# DCDC_Buck_Boost.net
KiCad netlist of a schematic drawn in Altium Designer
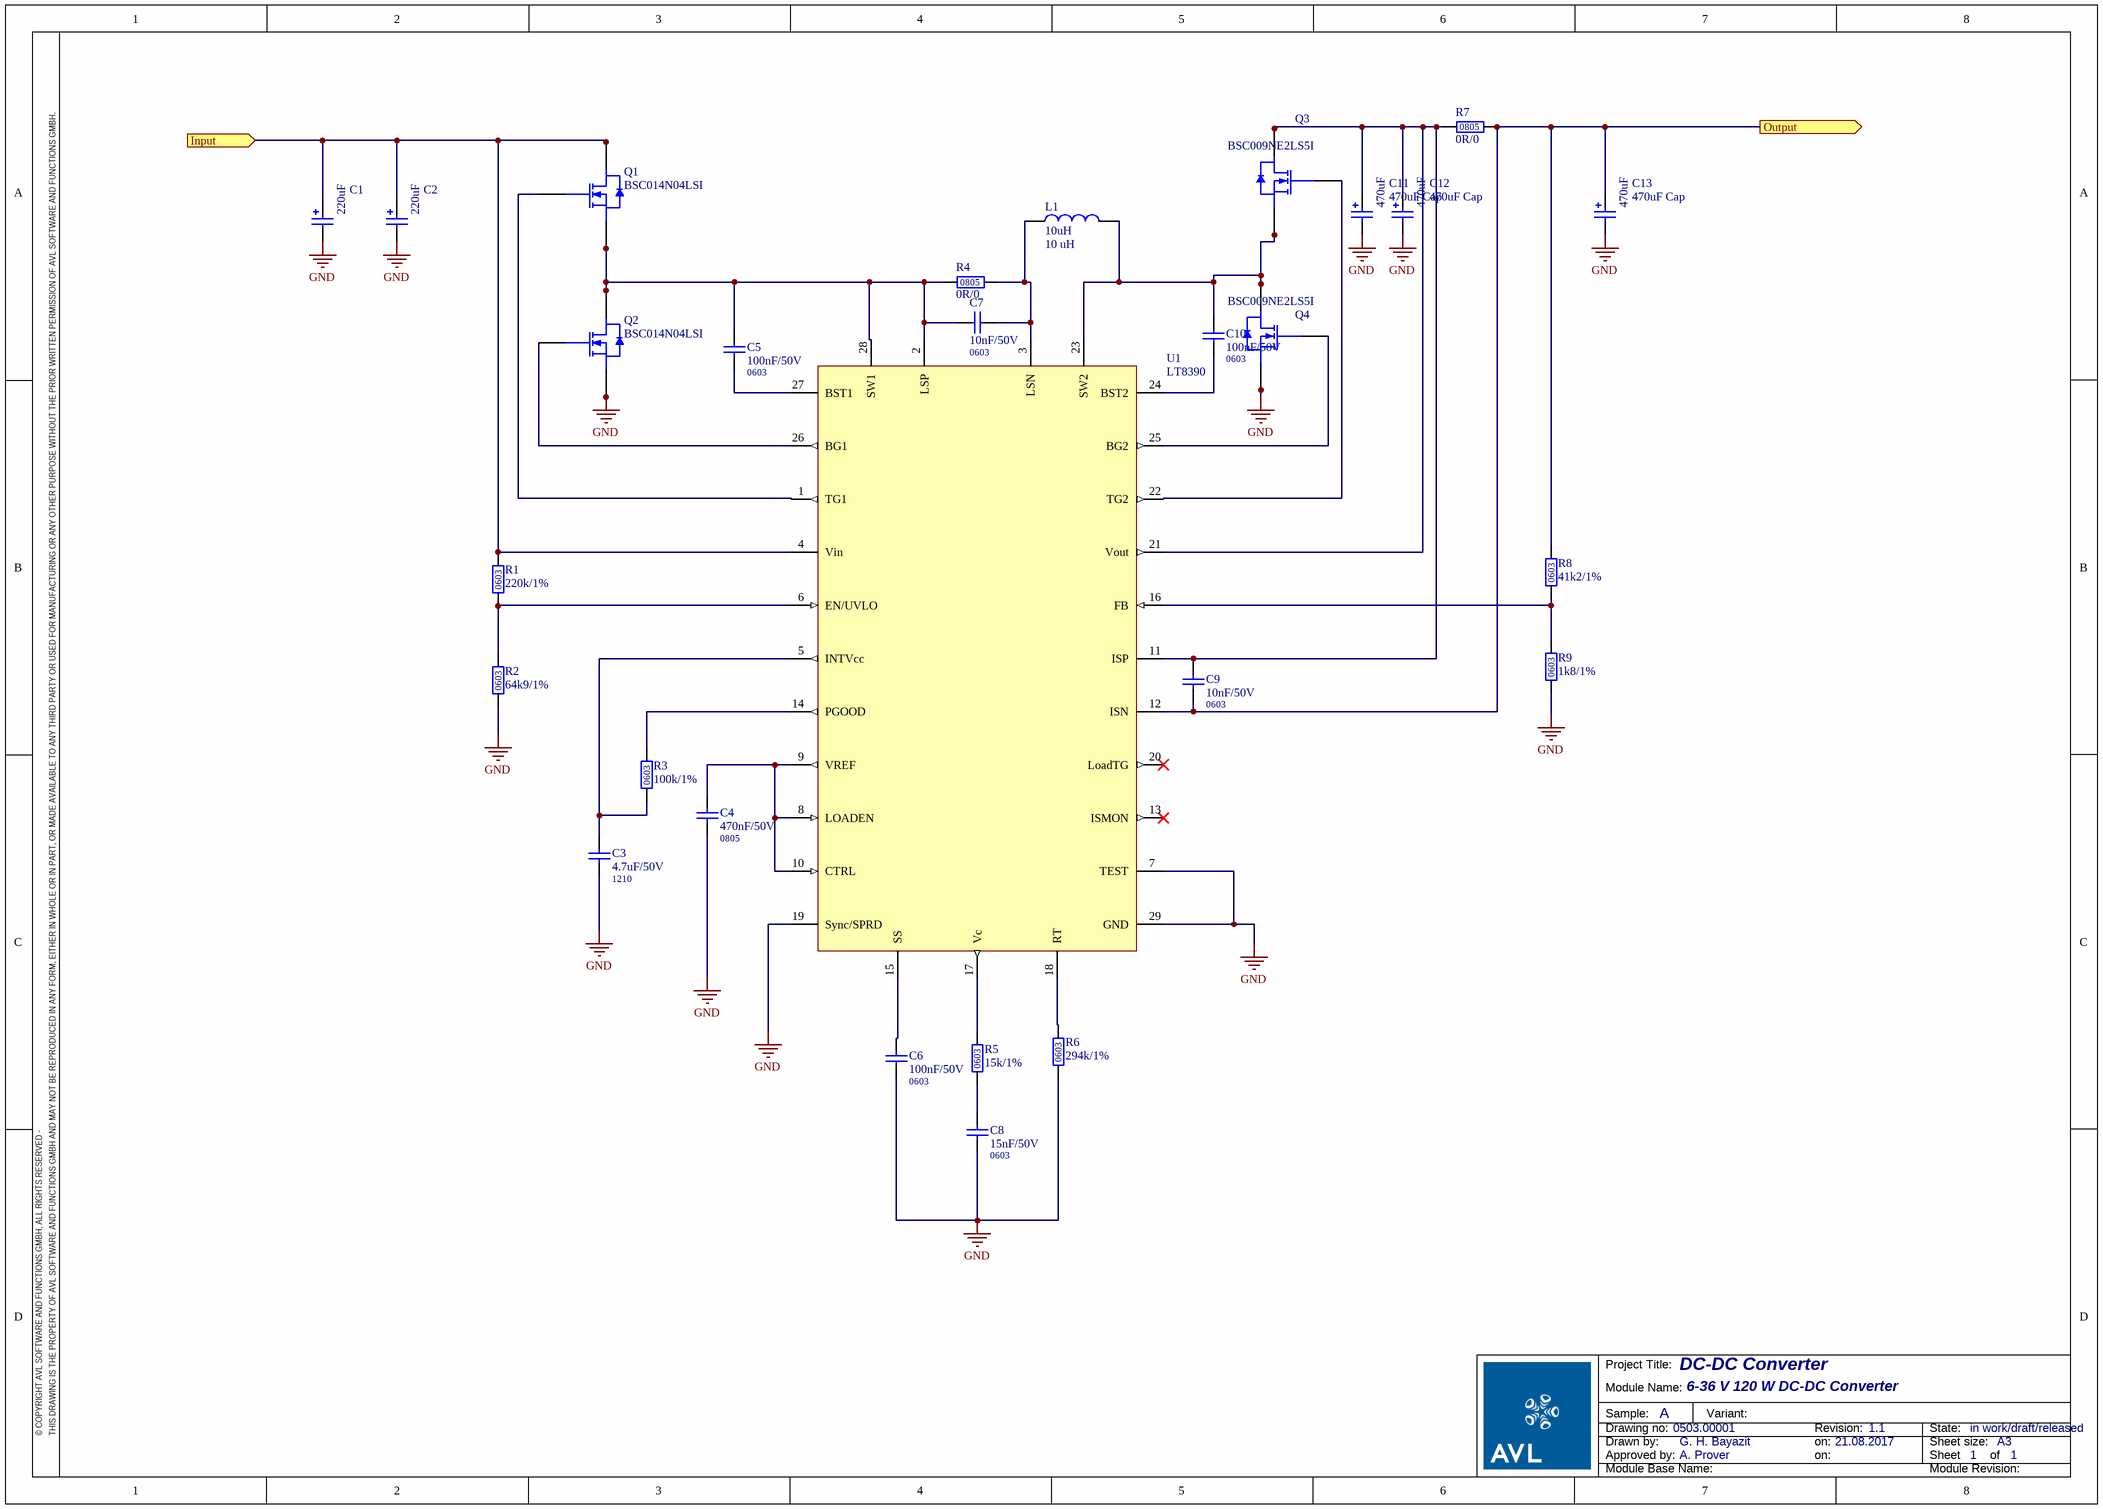
[diagram p0: DCDC_Buck_Boost.SchDoc]

(export (version "E")
  (design (tool "Eeschema 10.0.6"))
  (components
    (comp (ref "C1")
      (value "220uF Cap")
      (footprint "PcbLib:WCAP-ASLI_4x5.5")
      (libsource (lib "SchLib") (part "220uF Cap"))
    )
    (comp (ref "C2")
      (value "220uF Cap")
      (footprint "PcbLib:WCAP-ASLI_4x5.5")
      (libsource (lib "SchLib") (part "220uF Cap"))
    )
    (comp (ref "C3")
      (value "4.7uF/50V")
      (footprint "CAPC3225X30")
      (fields
        (field (name "VOLTAGE") "50V")
        (field (name "PACKAGE") "1210")
        (field (name "PART_NUMBER") "0444.00103")
        (field (name "MANUFACTURER") "Murata")
      )
      (libsource (lib "AVL_EHW_Comp_Lib") (part "Capacitor"))
    )
    (comp (ref "C4")
      (value "470nF/50V")
      (footprint "CAPC2012X15")
      (fields
        (field (name "VOLTAGE") "50V")
        (field (name "PACKAGE") "0805")
        (field (name "PART_NUMBER") "0444.00090")
        (field (name "MANUFACTURER") "Murata")
      )
      (libsource (lib "AVL_EHW_Comp_Lib") (part "Capacitor"))
    )
    (comp (ref "C5")
      (value "100nF/50V")
      (footprint "CAPC1608X10")
      (fields
        (field (name "VOLTAGE") "50V")
        (field (name "PACKAGE") "0603")
        (field (name "PART_NUMBER") "0444.00073")
        (field (name "MANUFACTURER") "Murata")
      )
      (libsource (lib "AVL_EHW_Comp_Lib") (part "Capacitor"))
    )
    (comp (ref "C6")
      (value "100nF/50V")
      (footprint "CAPC1608X10")
      (fields
        (field (name "VOLTAGE") "50V")
        (field (name "PACKAGE") "0603")
        (field (name "PART_NUMBER") "0444.00073")
        (field (name "MANUFACTURER") "Murata")
      )
      (libsource (lib "AVL_EHW_Comp_Lib") (part "Capacitor"))
    )
    (comp (ref "C7")
      (value "10nF/50V")
      (footprint "CAPC1608X10")
      (fields
        (field (name "VOLTAGE") "50V")
        (field (name "PACKAGE") "0603")
        (field (name "PART_NUMBER") "0444.00053")
        (field (name "MANUFACTURER") "Murata")
      )
      (libsource (lib "AVL_EHW_Comp_Lib") (part "Capacitor"))
    )
    (comp (ref "C8")
      (value "15nF/50V")
      (footprint "CAPC1608X10")
      (fields
        (field (name "VOLTAGE") "50V")
        (field (name "PACKAGE") "0603")
        (field (name "PART_NUMBER") "0444.00059")
        (field (name "MANUFACTURER") "Murata")
      )
      (libsource (lib "AVL_EHW_Comp_Lib") (part "Capacitor"))
    )
    (comp (ref "C9")
      (value "10nF/50V")
      (footprint "CAPC1608X10")
      (fields
        (field (name "VOLTAGE") "50V")
        (field (name "PACKAGE") "0603")
        (field (name "PART_NUMBER") "0444.00053")
        (field (name "MANUFACTURER") "Murata")
      )
      (libsource (lib "AVL_EHW_Comp_Lib") (part "Capacitor"))
    )
    (comp (ref "C10")
      (value "100nF/50V")
      (footprint "CAPC1608X10")
      (fields
        (field (name "VOLTAGE") "50V")
        (field (name "PACKAGE") "0603")
        (field (name "PART_NUMBER") "0444.00073")
        (field (name "MANUFACTURER") "Murata")
      )
      (libsource (lib "AVL_EHW_Comp_Lib") (part "Capacitor"))
    )
    (comp (ref "C11")
      (value "470uF Cap")
      (footprint "PcbLib:WCAP-ASLL_4x5.5")
      (libsource (lib "SchLib") (part "470uF Cap"))
    )
    (comp (ref "C12")
      (value "470uF Cap")
      (footprint "PcbLib:WCAP-ASLL_4x5.5")
      (libsource (lib "SchLib") (part "470uF Cap"))
    )
    (comp (ref "C13")
      (value "470uF Cap")
      (footprint "PcbLib:WCAP-ASLL_4x5.5")
      (libsource (lib "SchLib") (part "470uF Cap"))
    )
    (comp (ref "L1")
      (value "10uH")
      (footprint "PcbLib:WE-HCF_2818")
      (description "WE-HCF SMD High Current Inductor, size 2818, 10 uH")
      (fields
        (field (name "PART NUMBER") "7443641000")
        (field (name "ALTIUM_VALUE") "10 uH")
        (field (name "PUBLISHER") "Wurth Elektronik")
      )
      (libsource (lib "SchLib") (part "10uH"))
    )
    (comp (ref "Q1")
      (value "BSC014N04LSI")
      (footprint "PcbLib:TDSON-8-FL")
      (libsource (lib "SchLib") (part "BSC014N04LSI"))
    )
    (comp (ref "Q2")
      (value "BSC014N04LSI")
      (footprint "PcbLib:TDSON-8-FL")
      (libsource (lib "SchLib") (part "BSC014N04LSI"))
    )
    (comp (ref "Q3")
      (value "BSC009NE2LS5I")
      (footprint "PcbLib:TDSON-8-FL")
      (libsource (lib "SchLib") (part "BSC009NE2LS5I"))
    )
    (comp (ref "Q4")
      (value "BSC009NE2LS5I")
      (footprint "PcbLib:TDSON-8-FL")
      (libsource (lib "SchLib") (part "BSC009NE2LS5I"))
    )
    (comp (ref "R1")
      (value "220k/1%")
      (footprint "RESC1608X05")
      (fields
        (field (name "TOLERANCE") "1%")
        (field (name "PACKAGE") "0603")
        (field (name "PART_NUMBER") "0440.00197")
        (field (name "MANUFACTURER") "Vishay")
      )
      (libsource (lib "AVL_EHW_Comp_Lib") (part "Resistor-Chip"))
    )
    (comp (ref "R2")
      (value "64k9/1%")
      (footprint "RESC1608X05")
      (fields
        (field (name "TOLERANCE") "1%")
        (field (name "PACKAGE") "0603")
        (field (name "PART_NUMBER") "0440.00282")
        (field (name "MANUFACTURER") "Vishay")
      )
      (libsource (lib "AVL_EHW_Comp_Lib") (part "Resistor-Chip"))
    )
    (comp (ref "R3")
      (value "100k/1%")
      (footprint "RESC1608X05")
      (fields
        (field (name "TOLERANCE") "1%")
        (field (name "PACKAGE") "0603")
        (field (name "PART_NUMBER") "0440.00176")
        (field (name "MANUFACTURER") "Vishay")
      )
      (libsource (lib "AVL_EHW_Comp_Lib") (part "Resistor-Chip"))
    )
    (comp (ref "R4")
      (value "0R/0")
      (footprint "RESC2012X05")
      (fields
        (field (name "TOLERANCE") "0")
        (field (name "PACKAGE") "0805")
        (field (name "PART_NUMBER") "0440.00003")
        (field (name "MANUFACTURER") "Vishay")
      )
      (libsource (lib "AVL_EHW_Comp_Lib") (part "Resistor-Chip"))
    )
    (comp (ref "R5")
      (value "15k/1%")
      (footprint "RESC1608X05")
      (fields
        (field (name "TOLERANCE") "1%")
        (field (name "PACKAGE") "0603")
        (field (name "PART_NUMBER") "0440.00148")
        (field (name "MANUFACTURER") "Vishay")
      )
      (libsource (lib "AVL_EHW_Comp_Lib") (part "Resistor-Chip"))
    )
    (comp (ref "R6")
      (value "294k/1%")
      (footprint "RESC1608X05")
      (fields
        (field (name "TOLERANCE") "1%")
        (field (name "PACKAGE") "0603")
        (field (name "PART_NUMBER") "0440.00329")
        (field (name "MANUFACTURER") "Vishay")
      )
      (libsource (lib "AVL_EHW_Comp_Lib") (part "Resistor-Chip"))
    )
    (comp (ref "R7")
      (value "0R/0")
      (footprint "RESC2012X05")
      (fields
        (field (name "TOLERANCE") "0")
        (field (name "PACKAGE") "0805")
        (field (name "PART_NUMBER") "0440.00003")
        (field (name "MANUFACTURER") "Vishay")
      )
      (libsource (lib "AVL_EHW_Comp_Lib") (part "Resistor-Chip"))
    )
    (comp (ref "R8")
      (value "41k2/1%")
      (footprint "RESC1608X05")
      (fields
        (field (name "TOLERANCE") "1%")
        (field (name "PACKAGE") "0603")
        (field (name "PART_NUMBER") "0440.00284")
        (field (name "MANUFACTURER") "Vishay")
      )
      (libsource (lib "AVL_EHW_Comp_Lib") (part "Resistor-Chip"))
    )
    (comp (ref "R9")
      (value "1k8/1%")
      (footprint "RESC1608X05")
      (fields
        (field (name "TOLERANCE") "1%")
        (field (name "PACKAGE") "0603")
        (field (name "PART_NUMBER") "0440.00105")
        (field (name "MANUFACTURER") "Vishay")
      )
      (libsource (lib "AVL_EHW_Comp_Lib") (part "Resistor-Chip"))
    )
    (comp (ref "U1")
      (value "LT8390")
      (footprint "LT3890")
      (libsource (lib "Schematic Components") (part "LT8390"))
    )
  )
  (nets
    (net (code "1") (name "/Input") (class "Default")
      (node (ref "C1") (pin "1") (pinfunction "P_1") (pintype "passive"))
      (node (ref "C2") (pin "1") (pinfunction "P_1") (pintype "passive"))
      (node (ref "Q1") (pin "5") (pinfunction "D_5") (pintype "passive"))
      (node (ref "Q1") (pin "6") (pinfunction "D_6") (pintype "passive"))
      (node (ref "Q1") (pin "7") (pinfunction "D_7") (pintype "passive"))
      (node (ref "Q1") (pin "8") (pinfunction "D_8") (pintype "passive"))
      (node (ref "R1") (pin "1") (pinfunction "1_1") (pintype "passive"))
      (node (ref "U1") (pin "4") (pinfunction "Vin_4") (pintype "power_in"))
    )
    (net (code "2") (name "/Output") (class "Default")
      (node (ref "C13") (pin "1") (pinfunction "P_1") (pintype "passive"))
      (node (ref "C9") (pin "2") (pinfunction "2_2") (pintype "passive"))
      (node (ref "R7") (pin "2") (pinfunction "2_2") (pintype "passive"))
      (node (ref "R8") (pin "2") (pinfunction "2_2") (pintype "passive"))
      (node (ref "U1") (pin "12") (pinfunction "ISN_12") (pintype "passive"))
    )
    (net (code "3") (name "GND") (class "Default")
      (node (ref "C1") (pin "2") (pinfunction "N_2") (pintype "passive"))
      (node (ref "C11") (pin "2") (pinfunction "N_2") (pintype "passive"))
      (node (ref "C12") (pin "2") (pinfunction "N_2") (pintype "passive"))
      (node (ref "C13") (pin "2") (pinfunction "N_2") (pintype "passive"))
      (node (ref "C2") (pin "2") (pinfunction "N_2") (pintype "passive"))
      (node (ref "C3") (pin "1") (pinfunction "1_1") (pintype "passive"))
      (node (ref "C4") (pin "1") (pinfunction "1_1") (pintype "passive"))
      (node (ref "C6") (pin "2") (pinfunction "2_2") (pintype "passive"))
      (node (ref "C8") (pin "2") (pinfunction "2_2") (pintype "passive"))
      (node (ref "Q2") (pin "1") (pinfunction "S_1") (pintype "passive"))
      (node (ref "Q2") (pin "2") (pinfunction "S_2") (pintype "passive"))
      (node (ref "Q2") (pin "3") (pinfunction "S_3") (pintype "passive"))
      (node (ref "Q4") (pin "1") (pinfunction "S_1") (pintype "passive"))
      (node (ref "Q4") (pin "2") (pinfunction "S_2") (pintype "passive"))
      (node (ref "Q4") (pin "3") (pinfunction "S_3") (pintype "passive"))
      (node (ref "R2") (pin "2") (pinfunction "2_2") (pintype "passive"))
      (node (ref "R6") (pin "2") (pinfunction "2_2") (pintype "passive"))
      (node (ref "R9") (pin "1") (pinfunction "1_1") (pintype "passive"))
      (node (ref "U1") (pin "19") (pinfunction "Sync/SPRD_19") (pintype "passive"))
      (node (ref "U1") (pin "29") (pinfunction "GND_29") (pintype "power_in"))
      (node (ref "U1") (pin "7") (pinfunction "TEST_7") (pintype "passive"))
    )
    (net (code "4") (name "Net-(C8-Pad1)") (class "Default")
      (node (ref "C8") (pin "1") (pinfunction "1_1") (pintype "passive"))
      (node (ref "R5") (pin "2") (pinfunction "2_2") (pintype "passive"))
    )
    (net (code "5") (name "Net-(C11-P)") (class "Default")
      (node (ref "C11") (pin "1") (pinfunction "P_1") (pintype "passive"))
      (node (ref "C12") (pin "1") (pinfunction "P_1") (pintype "passive"))
      (node (ref "C9") (pin "1") (pinfunction "1_1") (pintype "passive"))
      (node (ref "Q3") (pin "5") (pinfunction "D_5") (pintype "passive"))
      (node (ref "Q3") (pin "6") (pinfunction "D_6") (pintype "passive"))
      (node (ref "Q3") (pin "7") (pinfunction "D_7") (pintype "passive"))
      (node (ref "Q3") (pin "8") (pinfunction "D_8") (pintype "passive"))
      (node (ref "R7") (pin "1") (pinfunction "1_1") (pintype "passive"))
      (node (ref "U1") (pin "11") (pinfunction "ISP_11") (pintype "passive"))
      (node (ref "U1") (pin "21") (pinfunction "Vout_21") (pintype "output"))
    )
    (net (code "6") (name "Net-(Q1-G)") (class "Default")
      (node (ref "Q1") (pin "4") (pinfunction "G_4") (pintype "passive"))
      (node (ref "U1") (pin "1") (pinfunction "TG1_1") (pintype "output"))
    )
    (net (code "7") (name "Net-(Q2-G)") (class "Default")
      (node (ref "Q2") (pin "4") (pinfunction "G_4") (pintype "passive"))
      (node (ref "U1") (pin "26") (pinfunction "BG1_26") (pintype "output"))
    )
    (net (code "8") (name "Net-(Q3-G)") (class "Default")
      (node (ref "Q3") (pin "4") (pinfunction "G_4") (pintype "passive"))
      (node (ref "U1") (pin "22") (pinfunction "TG2_22") (pintype "output"))
    )
    (net (code "9") (name "Net-(Q4-G)") (class "Default")
      (node (ref "Q4") (pin "4") (pinfunction "G_4") (pintype "passive"))
      (node (ref "U1") (pin "25") (pinfunction "BG2_25") (pintype "output"))
    )
    (net (code "10") (name "Net-(U1-BST1)") (class "Default")
      (node (ref "C5") (pin "2") (pinfunction "2_2") (pintype "passive"))
      (node (ref "U1") (pin "27") (pinfunction "BST1_27") (pintype "passive"))
    )
    (net (code "11") (name "Net-(U1-BST2)") (class "Default")
      (node (ref "C10") (pin "2") (pinfunction "2_2") (pintype "passive"))
      (node (ref "U1") (pin "24") (pinfunction "BST2_24") (pintype "passive"))
    )
    (net (code "12") (name "Net-(U1-CTRL)") (class "Default")
      (node (ref "C4") (pin "2") (pinfunction "2_2") (pintype "passive"))
      (node (ref "U1") (pin "10") (pinfunction "CTRL_10") (pintype "input"))
      (node (ref "U1") (pin "8") (pinfunction "LOADEN_8") (pintype "input"))
      (node (ref "U1") (pin "9") (pinfunction "VREF_9") (pintype "output"))
    )
    (net (code "13") (name "Net-(U1-EN{slash}UVLO)") (class "Default")
      (node (ref "R1") (pin "2") (pinfunction "2_2") (pintype "passive"))
      (node (ref "R2") (pin "1") (pinfunction "1_1") (pintype "passive"))
      (node (ref "U1") (pin "6") (pinfunction "EN/UVLO_6") (pintype "input"))
    )
    (net (code "14") (name "Net-(U1-FB)") (class "Default")
      (node (ref "R8") (pin "1") (pinfunction "1_1") (pintype "passive"))
      (node (ref "R9") (pin "2") (pinfunction "2_2") (pintype "passive"))
      (node (ref "U1") (pin "16") (pinfunction "FB_16") (pintype "input"))
    )
    (net (code "15") (name "Net-(U1-INTVcc)") (class "Default")
      (node (ref "C3") (pin "2") (pinfunction "2_2") (pintype "passive"))
      (node (ref "R3") (pin "1") (pinfunction "1_1") (pintype "passive"))
      (node (ref "U1") (pin "5") (pinfunction "INTVcc_5") (pintype "output"))
    )
    (net (code "16") (name "Net-(U1-LSN)") (class "Default")
      (node (ref "C7") (pin "1") (pinfunction "1_1") (pintype "passive"))
      (node (ref "L1") (pin "1") (pinfunction "1_1") (pintype "passive"))
      (node (ref "R4") (pin "2") (pinfunction "2_2") (pintype "passive"))
      (node (ref "U1") (pin "3") (pinfunction "LSN_3") (pintype "passive"))
    )
    (net (code "17") (name "Net-(U1-LSP)") (class "Default")
      (node (ref "C5") (pin "1") (pinfunction "1_1") (pintype "passive"))
      (node (ref "C7") (pin "2") (pinfunction "2_2") (pintype "passive"))
      (node (ref "Q1") (pin "1") (pinfunction "S_1") (pintype "passive"))
      (node (ref "Q1") (pin "2") (pinfunction "S_2") (pintype "passive"))
      (node (ref "Q1") (pin "3") (pinfunction "S_3") (pintype "passive"))
      (node (ref "Q2") (pin "5") (pinfunction "D_5") (pintype "passive"))
      (node (ref "Q2") (pin "6") (pinfunction "D_6") (pintype "passive"))
      (node (ref "Q2") (pin "7") (pinfunction "D_7") (pintype "passive"))
      (node (ref "Q2") (pin "8") (pinfunction "D_8") (pintype "passive"))
      (node (ref "R4") (pin "1") (pinfunction "1_1") (pintype "passive"))
      (node (ref "U1") (pin "2") (pinfunction "LSP_2") (pintype "passive"))
      (node (ref "U1") (pin "28") (pinfunction "SW1_28") (pintype "passive"))
    )
    (net (code "18") (name "Net-(U1-PGOOD)") (class "Default")
      (node (ref "R3") (pin "2") (pinfunction "2_2") (pintype "passive"))
      (node (ref "U1") (pin "14") (pinfunction "PGOOD_14") (pintype "output"))
    )
    (net (code "19") (name "Net-(U1-RT)") (class "Default")
      (node (ref "R6") (pin "1") (pinfunction "1_1") (pintype "passive"))
      (node (ref "U1") (pin "18") (pinfunction "RT_18") (pintype "passive"))
    )
    (net (code "20") (name "Net-(U1-SS)") (class "Default")
      (node (ref "C6") (pin "1") (pinfunction "1_1") (pintype "passive"))
      (node (ref "U1") (pin "15") (pinfunction "SS_15") (pintype "passive"))
    )
    (net (code "21") (name "Net-(U1-SW2)") (class "Default")
      (node (ref "C10") (pin "1") (pinfunction "1_1") (pintype "passive"))
      (node (ref "L1") (pin "2") (pinfunction "2_2") (pintype "passive"))
      (node (ref "Q3") (pin "1") (pinfunction "S_1") (pintype "passive"))
      (node (ref "Q3") (pin "2") (pinfunction "S_2") (pintype "passive"))
      (node (ref "Q3") (pin "3") (pinfunction "S_3") (pintype "passive"))
      (node (ref "Q4") (pin "5") (pinfunction "D_5") (pintype "passive"))
      (node (ref "Q4") (pin "6") (pinfunction "D_6") (pintype "passive"))
      (node (ref "Q4") (pin "7") (pinfunction "D_7") (pintype "passive"))
      (node (ref "Q4") (pin "8") (pinfunction "D_8") (pintype "passive"))
      (node (ref "U1") (pin "23") (pinfunction "SW2_23") (pintype "passive"))
    )
    (net (code "22") (name "Net-(U1-Vc)") (class "Default")
      (node (ref "R5") (pin "1") (pinfunction "1_1") (pintype "passive"))
      (node (ref "U1") (pin "17") (pinfunction "Vc_17") (pintype "output"))
    )
    (net (code "23") (name "unconnected-(U1-ISMON-Pad13)") (class "Default")
      (node (ref "U1") (pin "13") (pinfunction "ISMON_13") (pintype "output+no_connect"))
    )
    (net (code "24") (name "unconnected-(U1-LoadTG-Pad20)") (class "Default")
      (node (ref "U1") (pin "20") (pinfunction "LoadTG_20") (pintype "output+no_connect"))
    )
  )
)
